# flasher.net
KiCad netlist of a schematic drawn in EAGLE
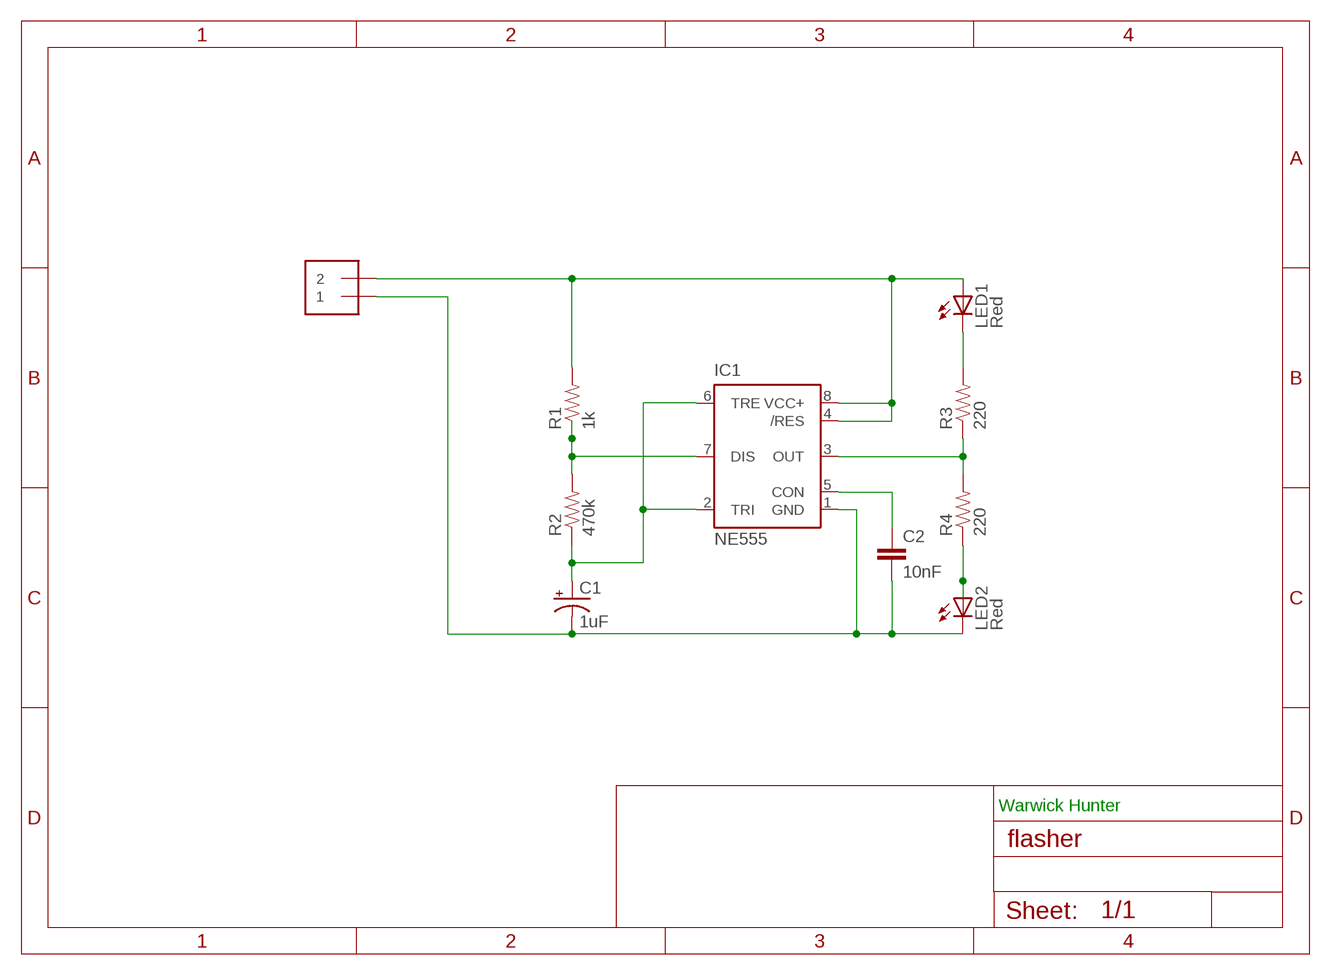
[diagram p0: schematic, sheet 1]

(export (version "E")
  (design (tool "Eeschema 10.0.6"))
  (components
    (comp (ref "C1")
      (value "1uF")
      (footprint "eagle-import:CPOL-RADIAL-10UF-25V")
      (libsource (lib "eagle-import") (part "CAP_POLPTH2"))
    )
    (comp (ref "C2")
      (value "10nF")
      (footprint "eagle-import:CAP-PTH-SMALL")
      (libsource (lib "eagle-import") (part "CAPPTH"))
    )
    (comp (ref "IC1")
      (value "NE555")
      (footprint "eagle-import:DIL-08")
      (fields (field (name "MF") "Arrow Electronics") (field (name "MPN") "NE555N"))
      (libsource (lib "eagle-import") (part "NE555"))
    )
    (comp (ref "J1")
      (value "1X2-3.5MM")
      (footprint "eagle-import:1X2-3.5MM")
      (libsource (lib "eagle-import") (part "1X2-3.5MM"))
    )
    (comp (ref "LED1")
      (value "Red")
      (footprint "eagle-import:LED5MM")
      (libsource (lib "eagle-import") (part "LED5MM"))
    )
    (comp (ref "LED2")
      (value "Red")
      (footprint "eagle-import:LED5MM")
      (libsource (lib "eagle-import") (part "LED5MM"))
    )
    (comp (ref "R1")
      (value "1k")
      (footprint "eagle-import:AXIAL-0.3")
      (libsource (lib "eagle-import") (part "RESISTORAXIAL-0.3"))
    )
    (comp (ref "R2")
      (value "470k")
      (footprint "eagle-import:AXIAL-0.3")
      (libsource (lib "eagle-import") (part "RESISTORAXIAL-0.3"))
    )
    (comp (ref "R3")
      (value "220")
      (footprint "eagle-import:AXIAL-0.3")
      (libsource (lib "eagle-import") (part "RESISTORAXIAL-0.3"))
    )
    (comp (ref "R4")
      (value "220")
      (footprint "eagle-import:AXIAL-0.3")
      (libsource (lib "eagle-import") (part "RESISTORAXIAL-0.3"))
    )
  )
  (nets
    (net (code "1") (name "Net-(C1-+)") (class "Default")
      (node (ref "C1") (pin "1") (pinfunction "+_1") (pintype "passive"))
      (node (ref "IC1") (pin "2") (pinfunction "TRI_2") (pintype "input"))
      (node (ref "IC1") (pin "6") (pinfunction "TRE_6") (pintype "input"))
      (node (ref "R2") (pin "P$1") (pinfunction "1_P$1") (pintype "passive"))
    )
    (net (code "2") (name "Net-(C1--)") (class "Default")
      (node (ref "C1") (pin "2") (pinfunction "-_2") (pintype "passive"))
      (node (ref "C2") (pin "2") (pinfunction "2_2") (pintype "passive"))
      (node (ref "IC1") (pin "1") (pinfunction "GND_1") (pintype "power_in"))
      (node (ref "J1") (pin "1") (pinfunction "1_1") (pintype "passive"))
      (node (ref "LED2") (pin "K") (pinfunction "C_K") (pintype "passive"))
    )
    (net (code "3") (name "Net-(IC1-CON)") (class "Default")
      (node (ref "C2") (pin "1") (pinfunction "1_1") (pintype "passive"))
      (node (ref "IC1") (pin "5") (pinfunction "CON_5") (pintype "input"))
    )
    (net (code "4") (name "Net-(IC1-DIS)") (class "Default")
      (node (ref "IC1") (pin "7") (pinfunction "DIS_7") (pintype "input"))
      (node (ref "R1") (pin "P$1") (pinfunction "1_P$1") (pintype "passive"))
      (node (ref "R2") (pin "P$2") (pinfunction "2_P$2") (pintype "passive"))
    )
    (net (code "5") (name "Net-(IC1-OUT)") (class "Default")
      (node (ref "IC1") (pin "3") (pinfunction "OUT_3") (pintype "output"))
      (node (ref "R3") (pin "P$1") (pinfunction "1_P$1") (pintype "passive"))
      (node (ref "R4") (pin "P$2") (pinfunction "2_P$2") (pintype "passive"))
    )
    (net (code "6") (name "Net-(IC1-VCC+)") (class "Default")
      (node (ref "IC1") (pin "4") (pinfunction "/RES_4") (pintype "input"))
      (node (ref "IC1") (pin "8") (pinfunction "VCC+_8") (pintype "power_in"))
      (node (ref "J1") (pin "2") (pinfunction "2_2") (pintype "passive"))
      (node (ref "LED1") (pin "A") (pinfunction "A_A") (pintype "passive"))
      (node (ref "R1") (pin "P$2") (pinfunction "2_P$2") (pintype "passive"))
    )
    (net (code "7") (name "Net-(LED1-C)") (class "Default")
      (node (ref "LED1") (pin "K") (pinfunction "C_K") (pintype "passive"))
      (node (ref "R3") (pin "P$2") (pinfunction "2_P$2") (pintype "passive"))
    )
    (net (code "8") (name "Net-(R4-1)") (class "Default")
      (node (ref "LED2") (pin "A") (pinfunction "A_A") (pintype "passive"))
      (node (ref "R4") (pin "P$1") (pinfunction "1_P$1") (pintype "passive"))
    )
  )
)
